# RotatingDUTtarget.net
KiCad netlist of a schematic drawn in Altium Designer
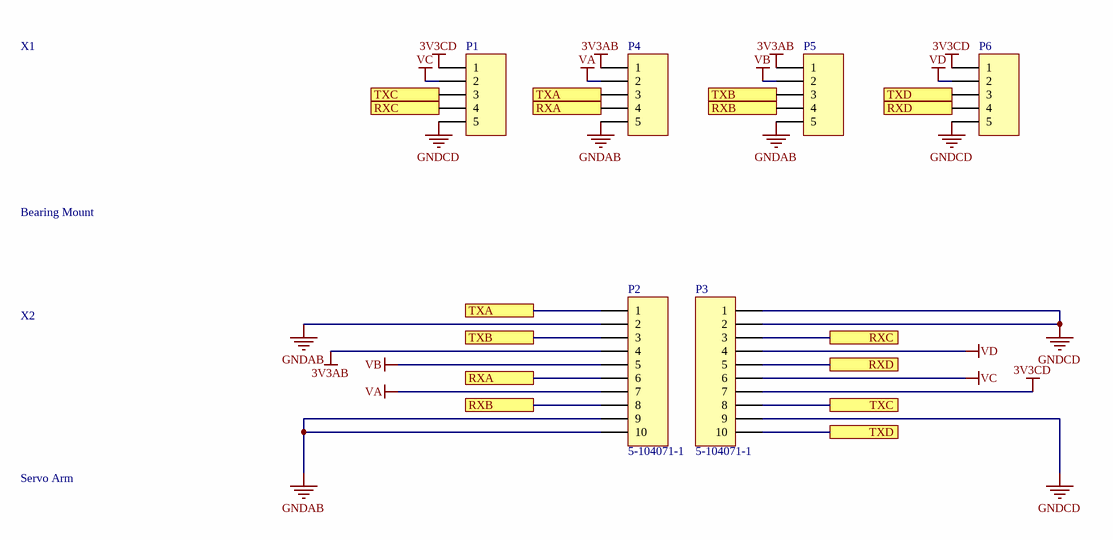
[diagram p0: RotatingDUTtarget.SchDoc]

(export (version "E")
  (design (tool "Eeschema 10.0.6"))
  (components
    (comp (ref "P1")
      (value "811-22-005-30-000101")
      (footprint "811-22-005-30-000101")
      (description "CONN SPRING CONT 05 POS .137 SMD")
      (fields (field (name "PART NUMBER") "PP-MMM-00001") (field (name "PUBLISHER") "AlbertaSat"))
      (libsource (lib "Database") (part "Header 5"))
    )
    (comp (ref "P2")
      (value "5-104071-1")
      (footprint "TEC-5-104071-1")
      (description "CONN HEADER 10POS .050 VERT GOLD")
      (fields (field (name "PART NUMBER") "458") (field (name "PUBLISHER") "Altium Limited"))
      (libsource (lib "Database") (part "Header 10"))
    )
    (comp (ref "P3")
      (value "5-104071-1")
      (footprint "TEC-5-104071-1")
      (description "CONN HEADER 10POS .050 VERT GOLD")
      (fields (field (name "PART NUMBER") "458") (field (name "PUBLISHER") "Altium Limited"))
      (libsource (lib "") (part "Header 10_1"))
    )
    (comp (ref "P4")
      (value "811-22-005-30-000101")
      (footprint "811-22-005-30-000101")
      (description "CONN SPRING CONT 05 POS .137 SMD")
      (fields (field (name "PART NUMBER") "PP-MMM-00001") (field (name "PUBLISHER") "AlbertaSat"))
      (libsource (lib "Database") (part "Header 5"))
    )
    (comp (ref "P5")
      (value "811-22-005-30-000101")
      (footprint "811-22-005-30-000101")
      (description "CONN SPRING CONT 05 POS .137 SMD")
      (fields (field (name "PART NUMBER") "PP-MMM-00001") (field (name "PUBLISHER") "AlbertaSat"))
      (libsource (lib "Database") (part "Header 5"))
    )
    (comp (ref "P6")
      (value "811-22-005-30-000101")
      (footprint "811-22-005-30-000101")
      (description "CONN SPRING CONT 05 POS .137 SMD")
      (fields (field (name "PART NUMBER") "PP-MMM-00001") (field (name "PUBLISHER") "AlbertaSat"))
      (libsource (lib "Database") (part "Header 5"))
    )
    (comp (ref "X1")
      (value "Bearing Mount")
      (footprint "Bearing Mount")
      (libsource (lib "Adapters") (part "Bearing Mount"))
    )
    (comp (ref "X2")
      (value "Servo Arm")
      (footprint "Servo Arm")
      (libsource (lib "Adapters") (part "Servo Arm"))
    )
  )
  (nets
    (net (code "1") (name "/RXA") (class "Default")
      (node (ref "P2") (pin "6") (pinfunction "6_6") (pintype "passive"))
      (node (ref "P4") (pin "4") (pinfunction "4_4") (pintype "passive"))
    )
    (net (code "2") (name "/RXB") (class "Default")
      (node (ref "P2") (pin "8") (pinfunction "8_8") (pintype "passive"))
      (node (ref "P5") (pin "4") (pinfunction "4_4") (pintype "passive"))
    )
    (net (code "3") (name "/RXC") (class "Default")
      (node (ref "P1") (pin "4") (pinfunction "4_4") (pintype "passive"))
      (node (ref "P3") (pin "3") (pinfunction "3_3") (pintype "passive"))
    )
    (net (code "4") (name "/RXD") (class "Default")
      (node (ref "P3") (pin "5") (pinfunction "5_5") (pintype "passive"))
      (node (ref "P6") (pin "4") (pinfunction "4_4") (pintype "passive"))
    )
    (net (code "5") (name "/TXA") (class "Default")
      (node (ref "P2") (pin "1") (pinfunction "1_1") (pintype "passive"))
      (node (ref "P4") (pin "3") (pinfunction "3_3") (pintype "passive"))
    )
    (net (code "6") (name "/TXB") (class "Default")
      (node (ref "P2") (pin "3") (pinfunction "3_3") (pintype "passive"))
      (node (ref "P5") (pin "3") (pinfunction "3_3") (pintype "passive"))
    )
    (net (code "7") (name "/TXC") (class "Default")
      (node (ref "P1") (pin "3") (pinfunction "3_3") (pintype "passive"))
      (node (ref "P3") (pin "8") (pinfunction "8_8") (pintype "passive"))
    )
    (net (code "8") (name "/TXD") (class "Default")
      (node (ref "P3") (pin "10") (pinfunction "10_10") (pintype "passive"))
      (node (ref "P6") (pin "3") (pinfunction "3_3") (pintype "passive"))
    )
    (net (code "9") (name "3V3AB") (class "Default")
      (node (ref "P2") (pin "4") (pinfunction "4_4") (pintype "passive"))
      (node (ref "P4") (pin "1") (pinfunction "1_1") (pintype "passive"))
      (node (ref "P5") (pin "1") (pinfunction "1_1") (pintype "passive"))
    )
    (net (code "10") (name "3V3CD") (class "Default")
      (node (ref "P1") (pin "1") (pinfunction "1_1") (pintype "passive"))
      (node (ref "P3") (pin "7") (pinfunction "7_7") (pintype "passive"))
      (node (ref "P6") (pin "1") (pinfunction "1_1") (pintype "passive"))
    )
    (net (code "11") (name "GNDAB") (class "Default")
      (node (ref "P2") (pin "10") (pinfunction "10_10") (pintype "passive"))
      (node (ref "P2") (pin "2") (pinfunction "2_2") (pintype "passive"))
      (node (ref "P2") (pin "9") (pinfunction "9_9") (pintype "passive"))
      (node (ref "P4") (pin "5") (pinfunction "5_5") (pintype "passive"))
      (node (ref "P5") (pin "5") (pinfunction "5_5") (pintype "passive"))
    )
    (net (code "12") (name "GNDCD") (class "Default")
      (node (ref "P1") (pin "5") (pinfunction "5_5") (pintype "passive"))
      (node (ref "P3") (pin "1") (pinfunction "1_1") (pintype "passive"))
      (node (ref "P3") (pin "2") (pinfunction "2_2") (pintype "passive"))
      (node (ref "P3") (pin "9") (pinfunction "9_9") (pintype "passive"))
      (node (ref "P6") (pin "5") (pinfunction "5_5") (pintype "passive"))
    )
    (net (code "13") (name "VA") (class "Default")
      (node (ref "P2") (pin "7") (pinfunction "7_7") (pintype "passive"))
      (node (ref "P4") (pin "2") (pinfunction "2_2") (pintype "passive"))
    )
    (net (code "14") (name "VB") (class "Default")
      (node (ref "P2") (pin "5") (pinfunction "5_5") (pintype "passive"))
      (node (ref "P5") (pin "2") (pinfunction "2_2") (pintype "passive"))
    )
    (net (code "15") (name "VC") (class "Default")
      (node (ref "P1") (pin "2") (pinfunction "2_2") (pintype "passive"))
      (node (ref "P3") (pin "6") (pinfunction "6_6") (pintype "passive"))
    )
    (net (code "16") (name "VD") (class "Default")
      (node (ref "P3") (pin "4") (pinfunction "4_4") (pintype "passive"))
      (node (ref "P6") (pin "2") (pinfunction "2_2") (pintype "passive"))
    )
  )
)
